# subckt_LDO_EMI_filter.net
KiCad netlist of a schematic drawn in Altium Designer
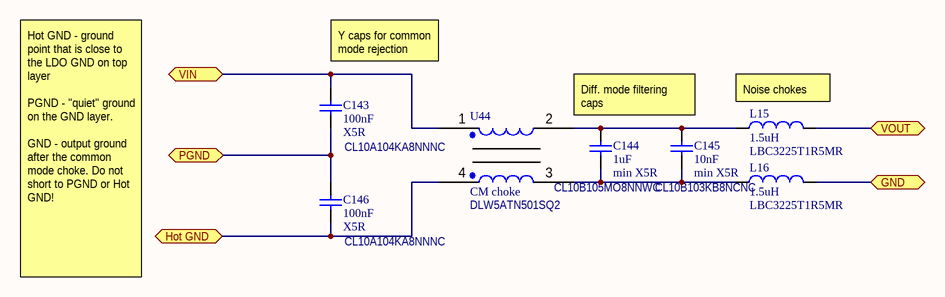
[diagram p0: subckt_LDO_EMI_filter.SchDoc]

(export (version "E")
  (design (tool "Eeschema 10.0.6"))
  (components
    (comp (ref "C143")
      (value "100nF")
      (footprint "CAP0603")
      (description "Capacitor")
      (fields (field (name "DIELECTRIC") "X5R") (field (name "MODEL") "CL10A104KA8NNNC"))
      (libsource (lib "lib_basic") (part "Capacitor"))
    )
    (comp (ref "C144")
      (value "1uF")
      (footprint "CAP0603")
      (description "Capacitor")
      (fields (field (name "DIELECTRIC") "min X5R") (field (name "MODEL") "CL10B105MO8NNWC"))
      (libsource (lib "lib_basic") (part "Capacitor"))
    )
    (comp (ref "C145")
      (value "10nF")
      (footprint "CAP0603")
      (description "Capacitor")
      (fields (field (name "DIELECTRIC") "min X5R") (field (name "MODEL") "CL10B103KB8NCNC"))
      (libsource (lib "lib_basic") (part "Capacitor"))
    )
    (comp (ref "C146")
      (value "100nF")
      (footprint "CAP0603")
      (description "Capacitor")
      (fields (field (name "DIELECTRIC") "X5R") (field (name "MODEL") "CL10A104KA8NNNC"))
      (libsource (lib "lib_basic") (part "Capacitor"))
    )
    (comp (ref "L15")
      (value "1.5uH")
      (footprint "lib_basic:IND 1210")
      (description "Inductor")
      (fields (field (name "MODEL") "LBC3225T1R5MR"))
      (libsource (lib "lib_basic") (part "Inductor"))
    )
    (comp (ref "L16")
      (value "1.5uH")
      (footprint "lib_basic:IND 1210")
      (description "Inductor")
      (fields (field (name "MODEL") "LBC3225T1R5MR"))
      (libsource (lib "lib_basic") (part "Inductor"))
    )
    (comp (ref "U44")
      (value "CM choke")
      (footprint "lib_power:Murata_DLW5A/5B")
      (description "Common mode choke")
      (fields (field (name "MODEL") "DLW5ATN501SQ2"))
      (libsource (lib "lib_power") (part "Common_choke"))
    )
  )
  (nets
    (net (code "1") (name "/GND") (class "Default")
      (node (ref "L16") (pin "2") (pinfunction "2_2") (pintype "passive"))
    )
    (net (code "2") (name "/Hot GND") (class "Default")
      (node (ref "C146") (pin "1") (pinfunction "1_1") (pintype "passive"))
      (node (ref "U44") (pin "4") (pinfunction "4_4") (pintype "passive"))
    )
    (net (code "3") (name "/PGND") (class "Default")
      (node (ref "C143") (pin "1") (pinfunction "1_1") (pintype "passive"))
      (node (ref "C146") (pin "2") (pinfunction "2_2") (pintype "passive"))
    )
    (net (code "4") (name "/VIN") (class "Default")
      (node (ref "C143") (pin "2") (pinfunction "2_2") (pintype "passive"))
      (node (ref "U44") (pin "1") (pinfunction "1_1") (pintype "passive"))
    )
    (net (code "5") (name "/VOUT") (class "Default")
      (node (ref "L15") (pin "2") (pinfunction "2_2") (pintype "passive"))
    )
    (net (code "6") (name "Net-(C144-Pad1)") (class "Default")
      (node (ref "C144") (pin "1") (pinfunction "1_1") (pintype "passive"))
      (node (ref "C145") (pin "1") (pinfunction "1_1") (pintype "passive"))
      (node (ref "L16") (pin "1") (pinfunction "1_1") (pintype "passive"))
      (node (ref "U44") (pin "3") (pinfunction "3_3") (pintype "passive"))
    )
    (net (code "7") (name "Net-(C144-Pad2)") (class "Default")
      (node (ref "C144") (pin "2") (pinfunction "2_2") (pintype "passive"))
      (node (ref "C145") (pin "2") (pinfunction "2_2") (pintype "passive"))
      (node (ref "L15") (pin "1") (pinfunction "1_1") (pintype "passive"))
      (node (ref "U44") (pin "2") (pinfunction "2_2") (pintype "passive"))
    )
  )
)
